# VIVA_PIC16_with_battery.net
KiCad netlist of a schematic drawn in EAGLE
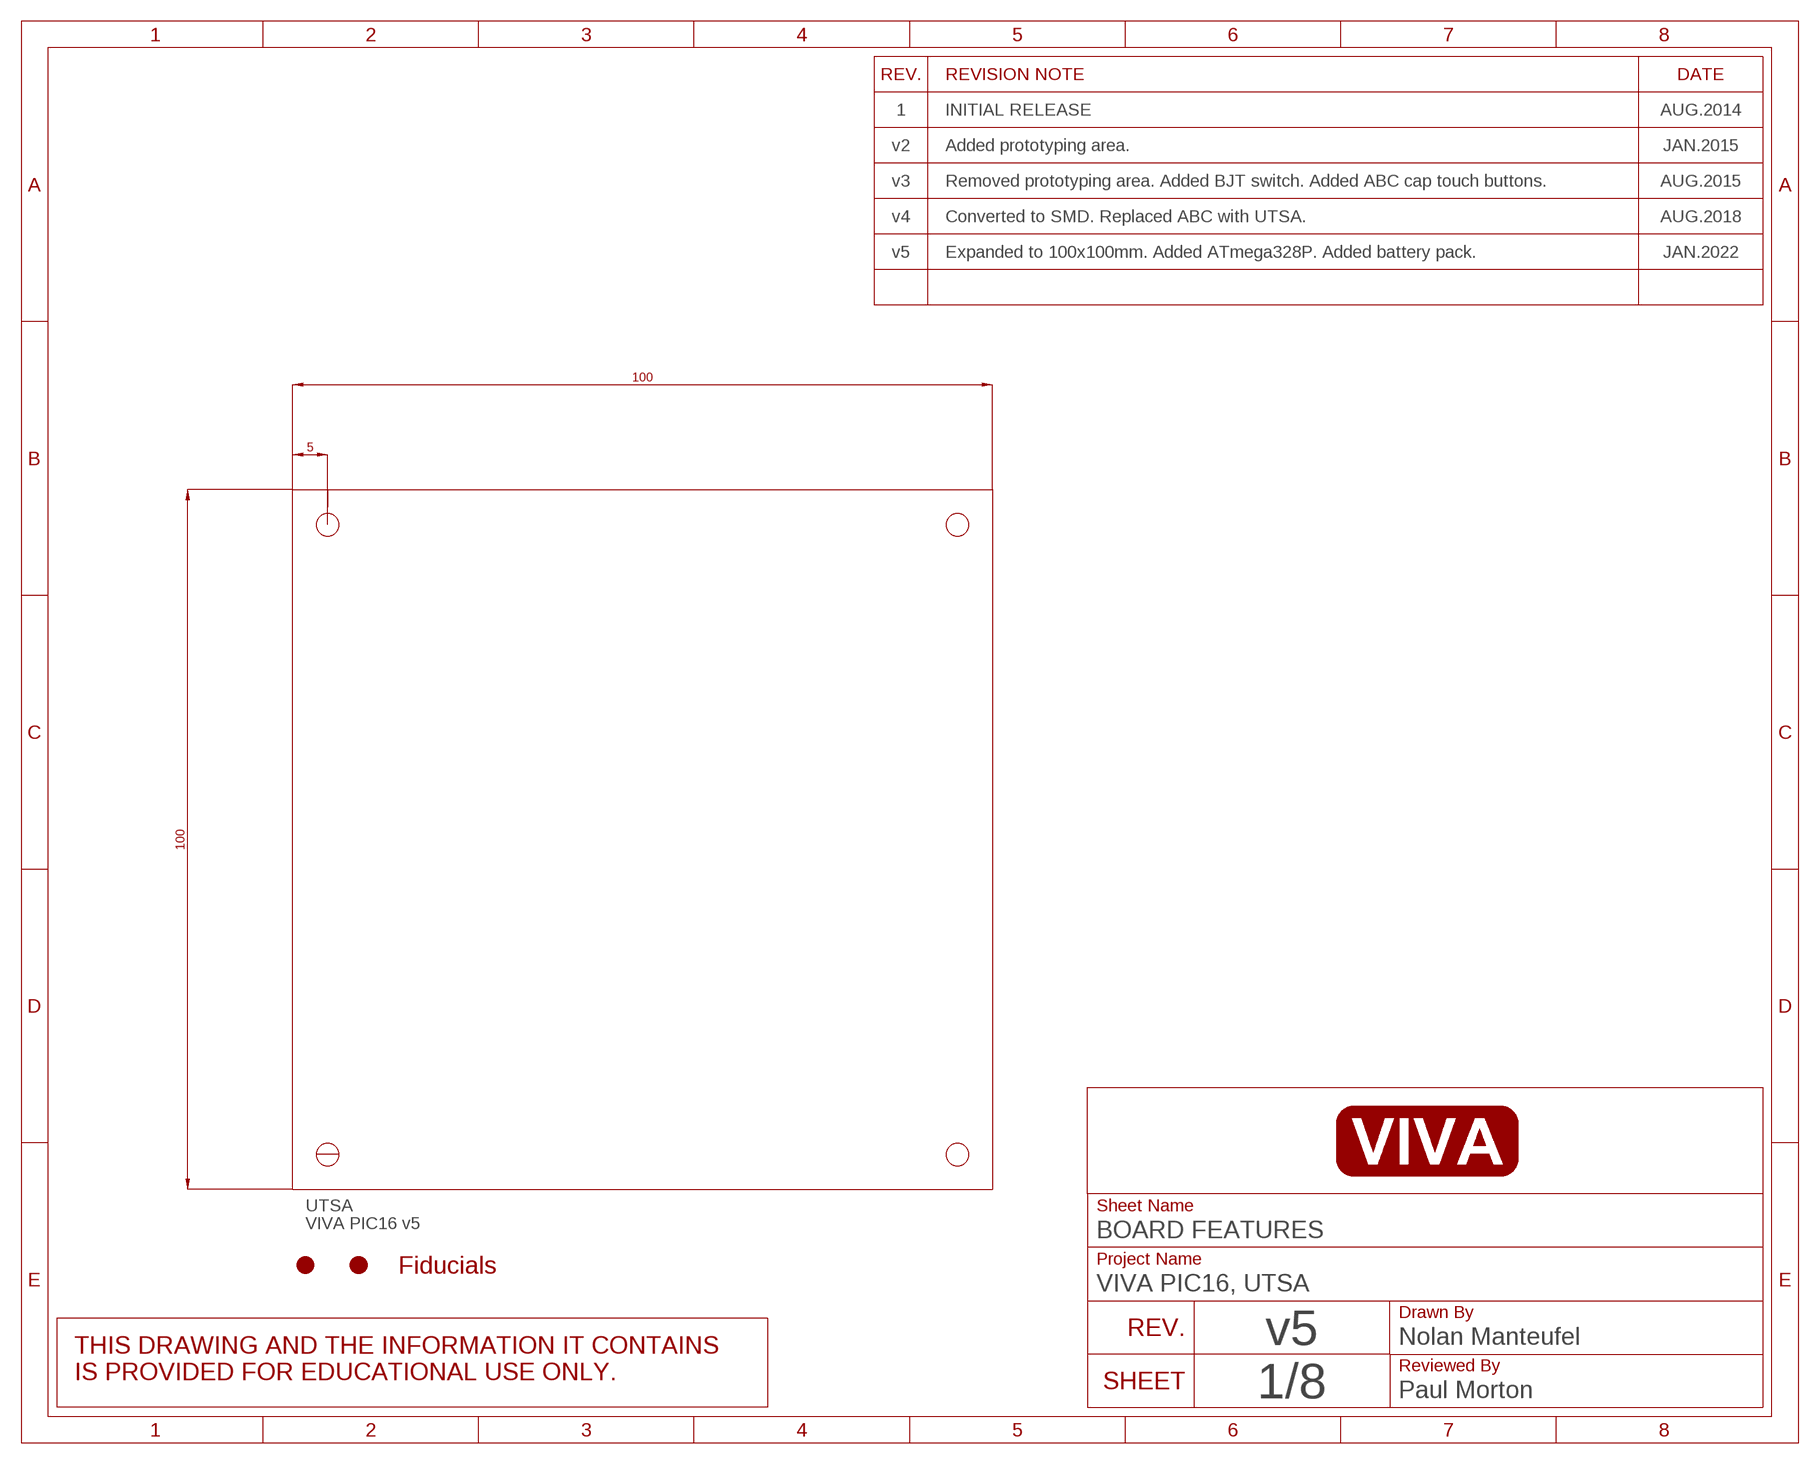
[diagram p0: schematic, sheet 1]
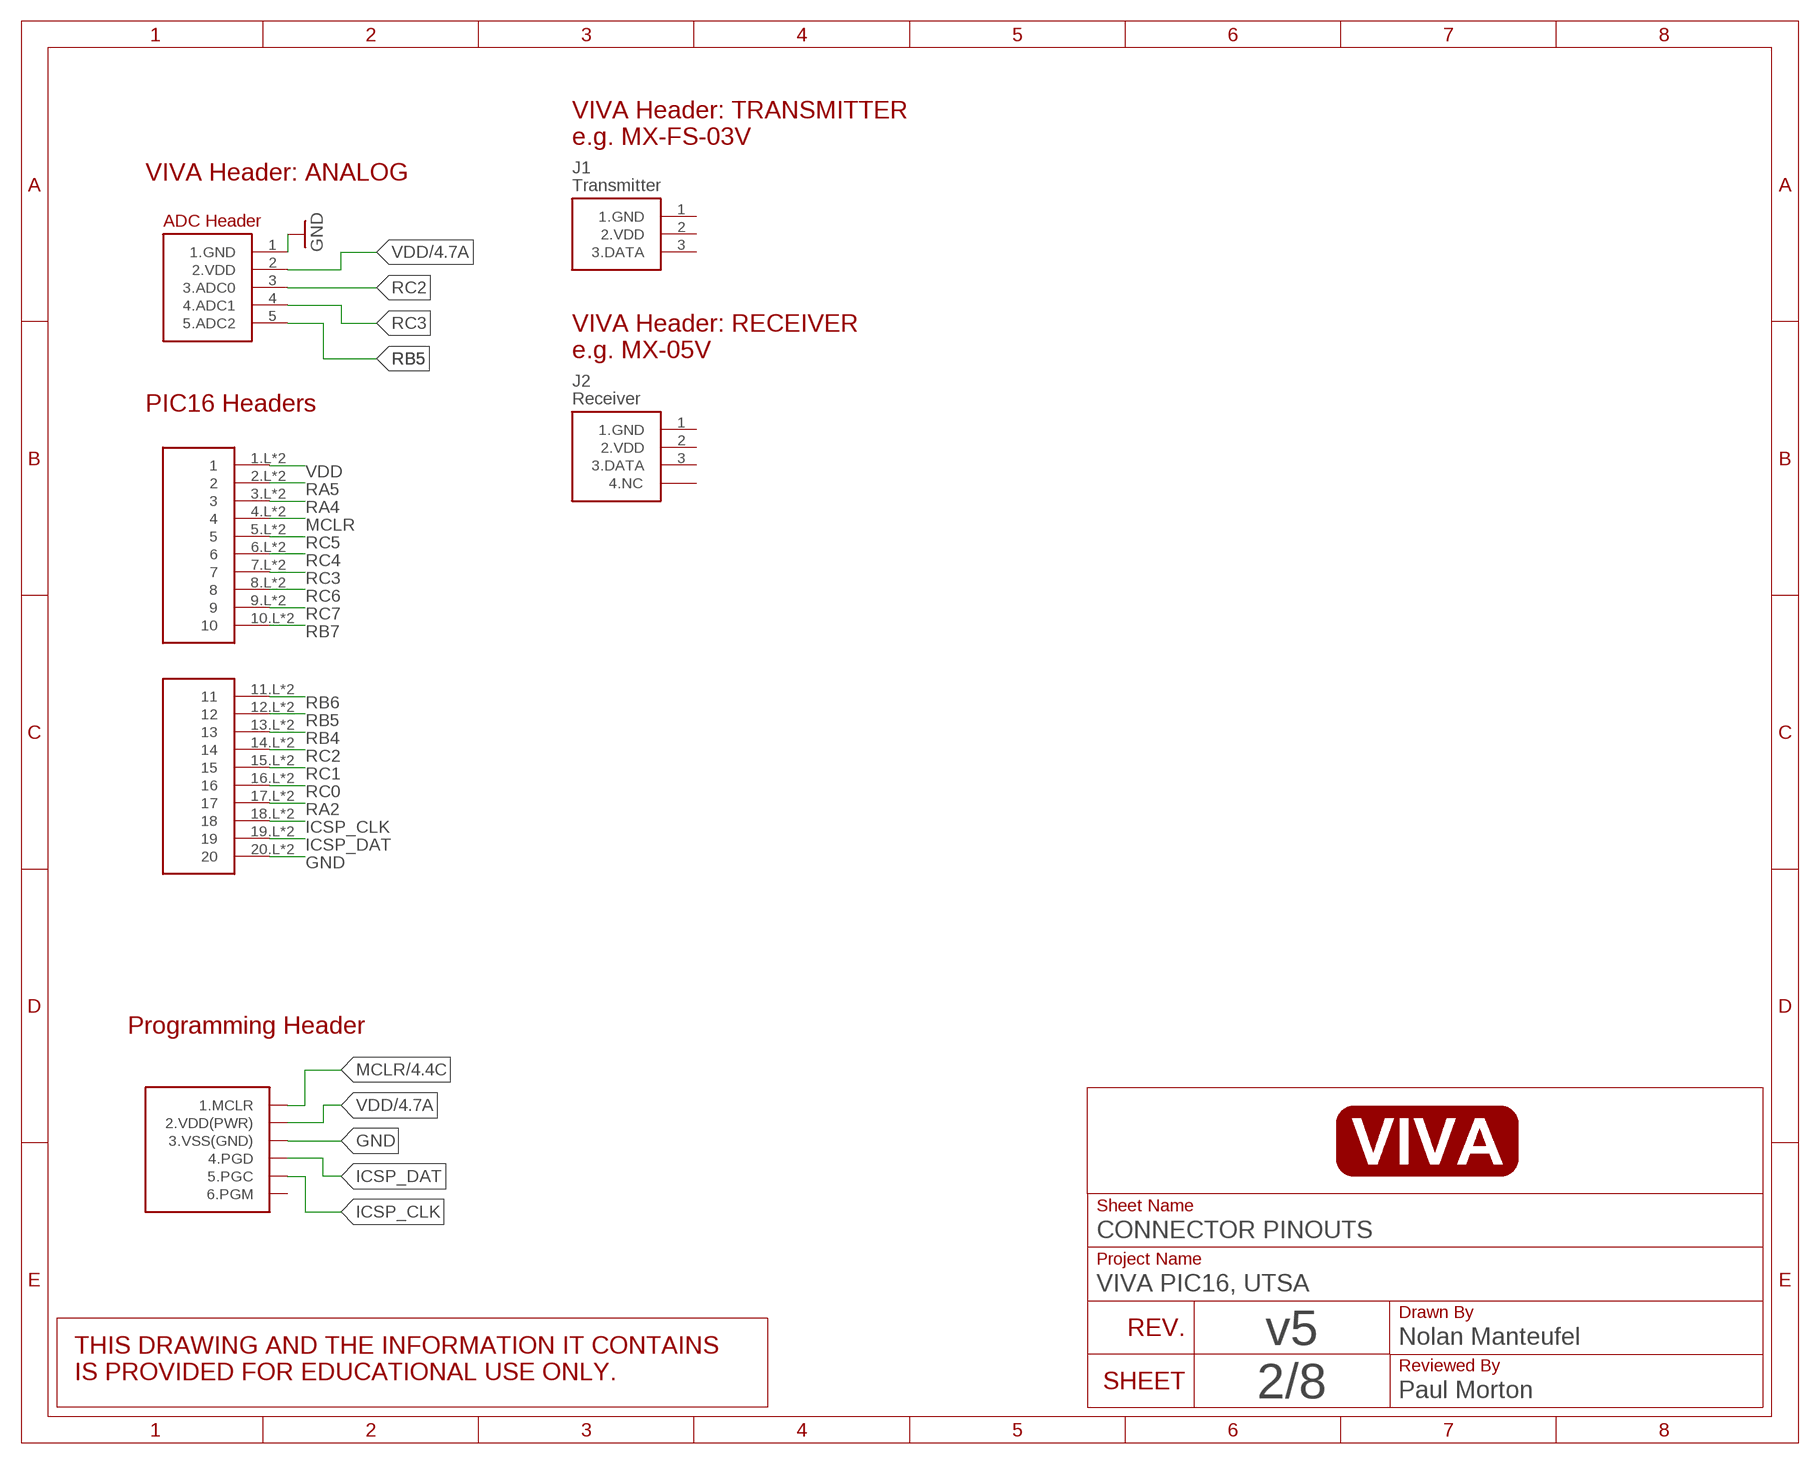
[diagram p1: schematic, sheet 2]
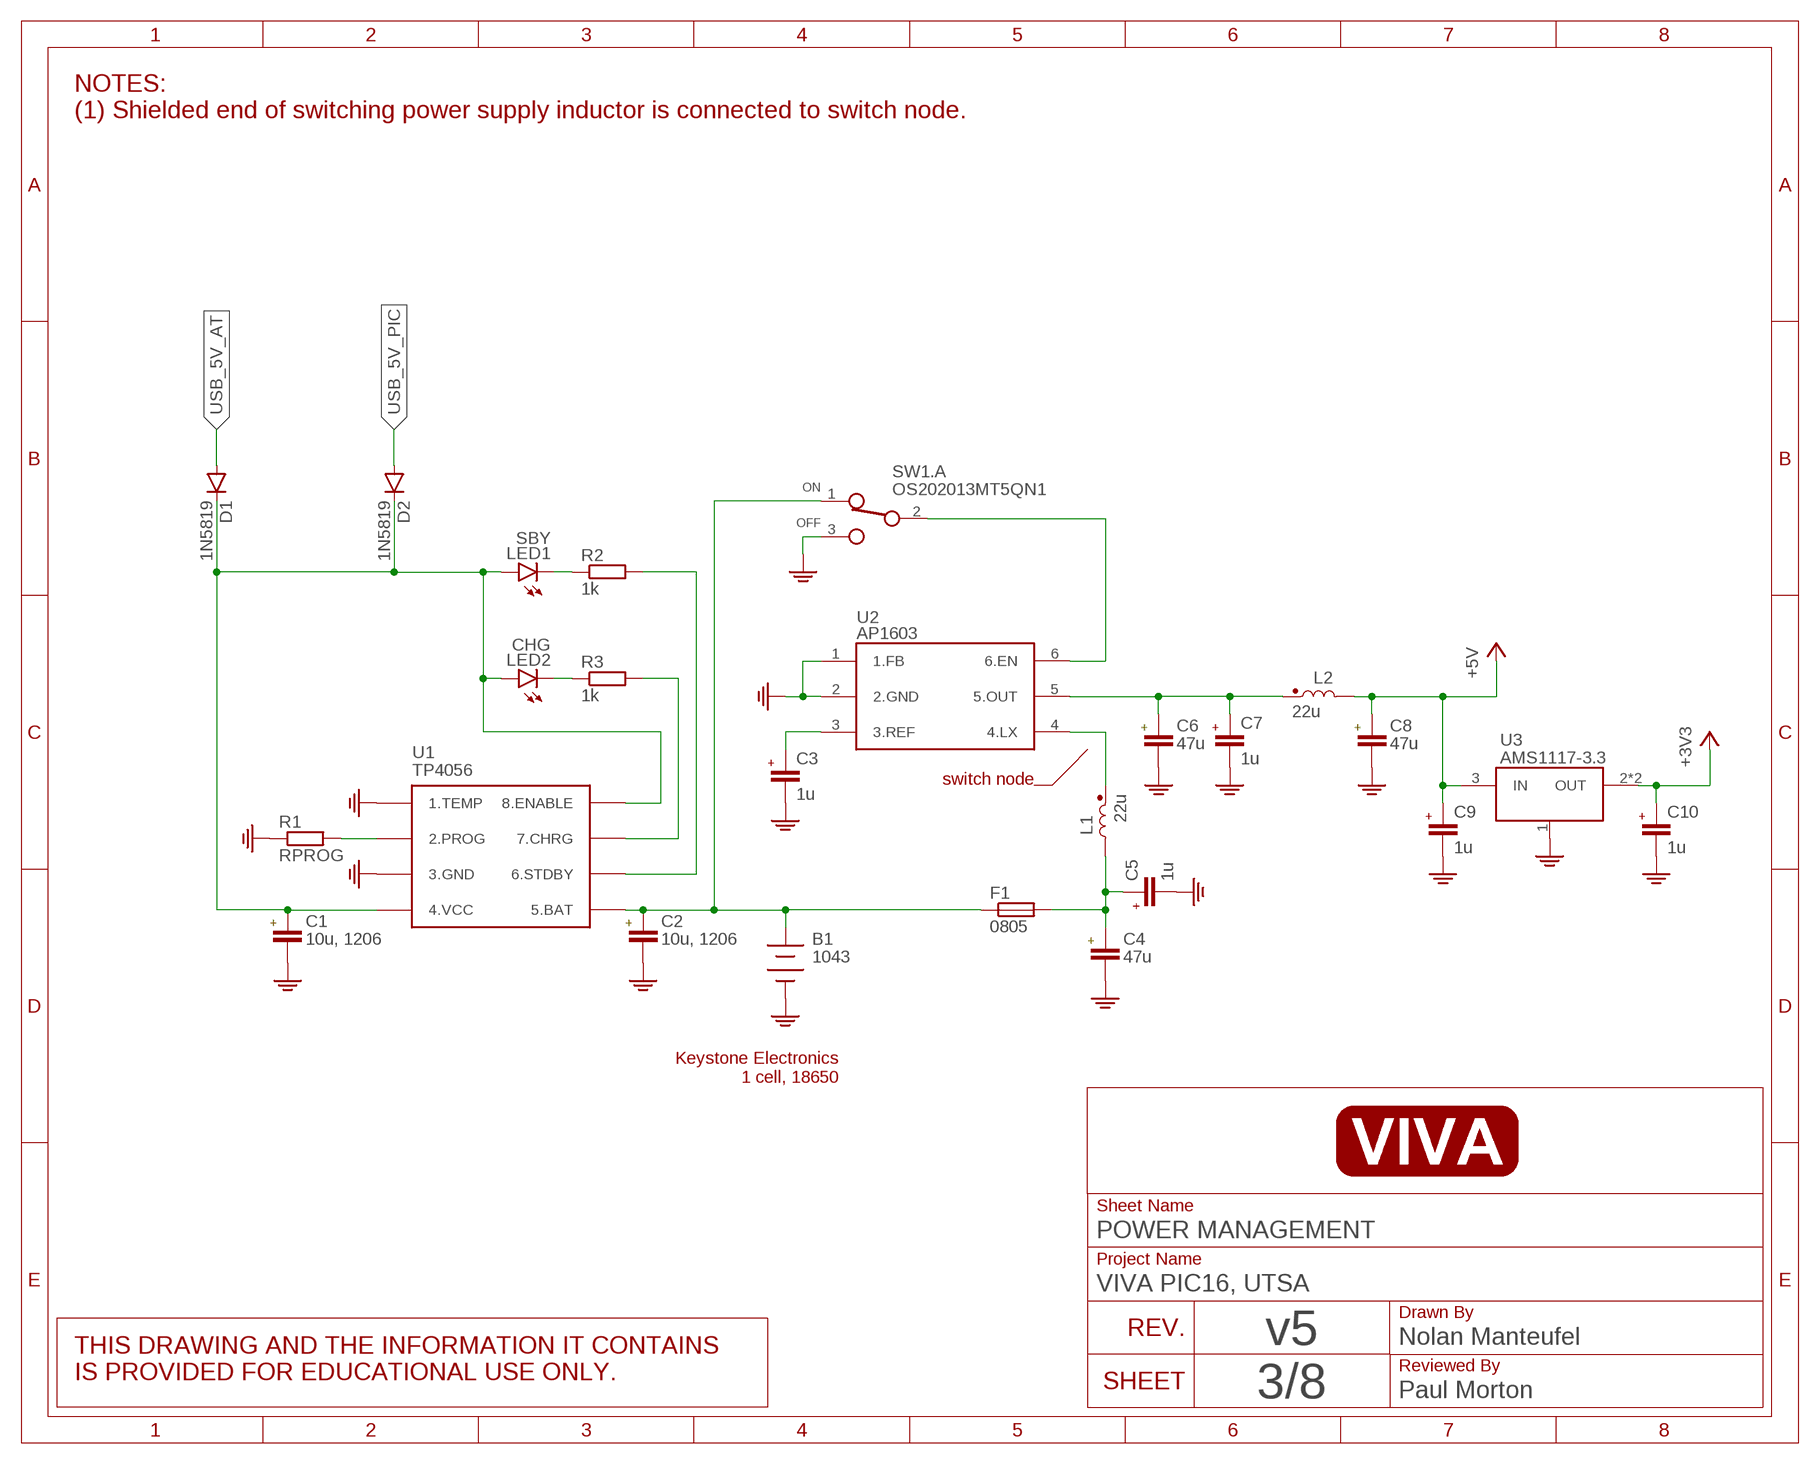
[diagram p2: schematic, sheet 3]
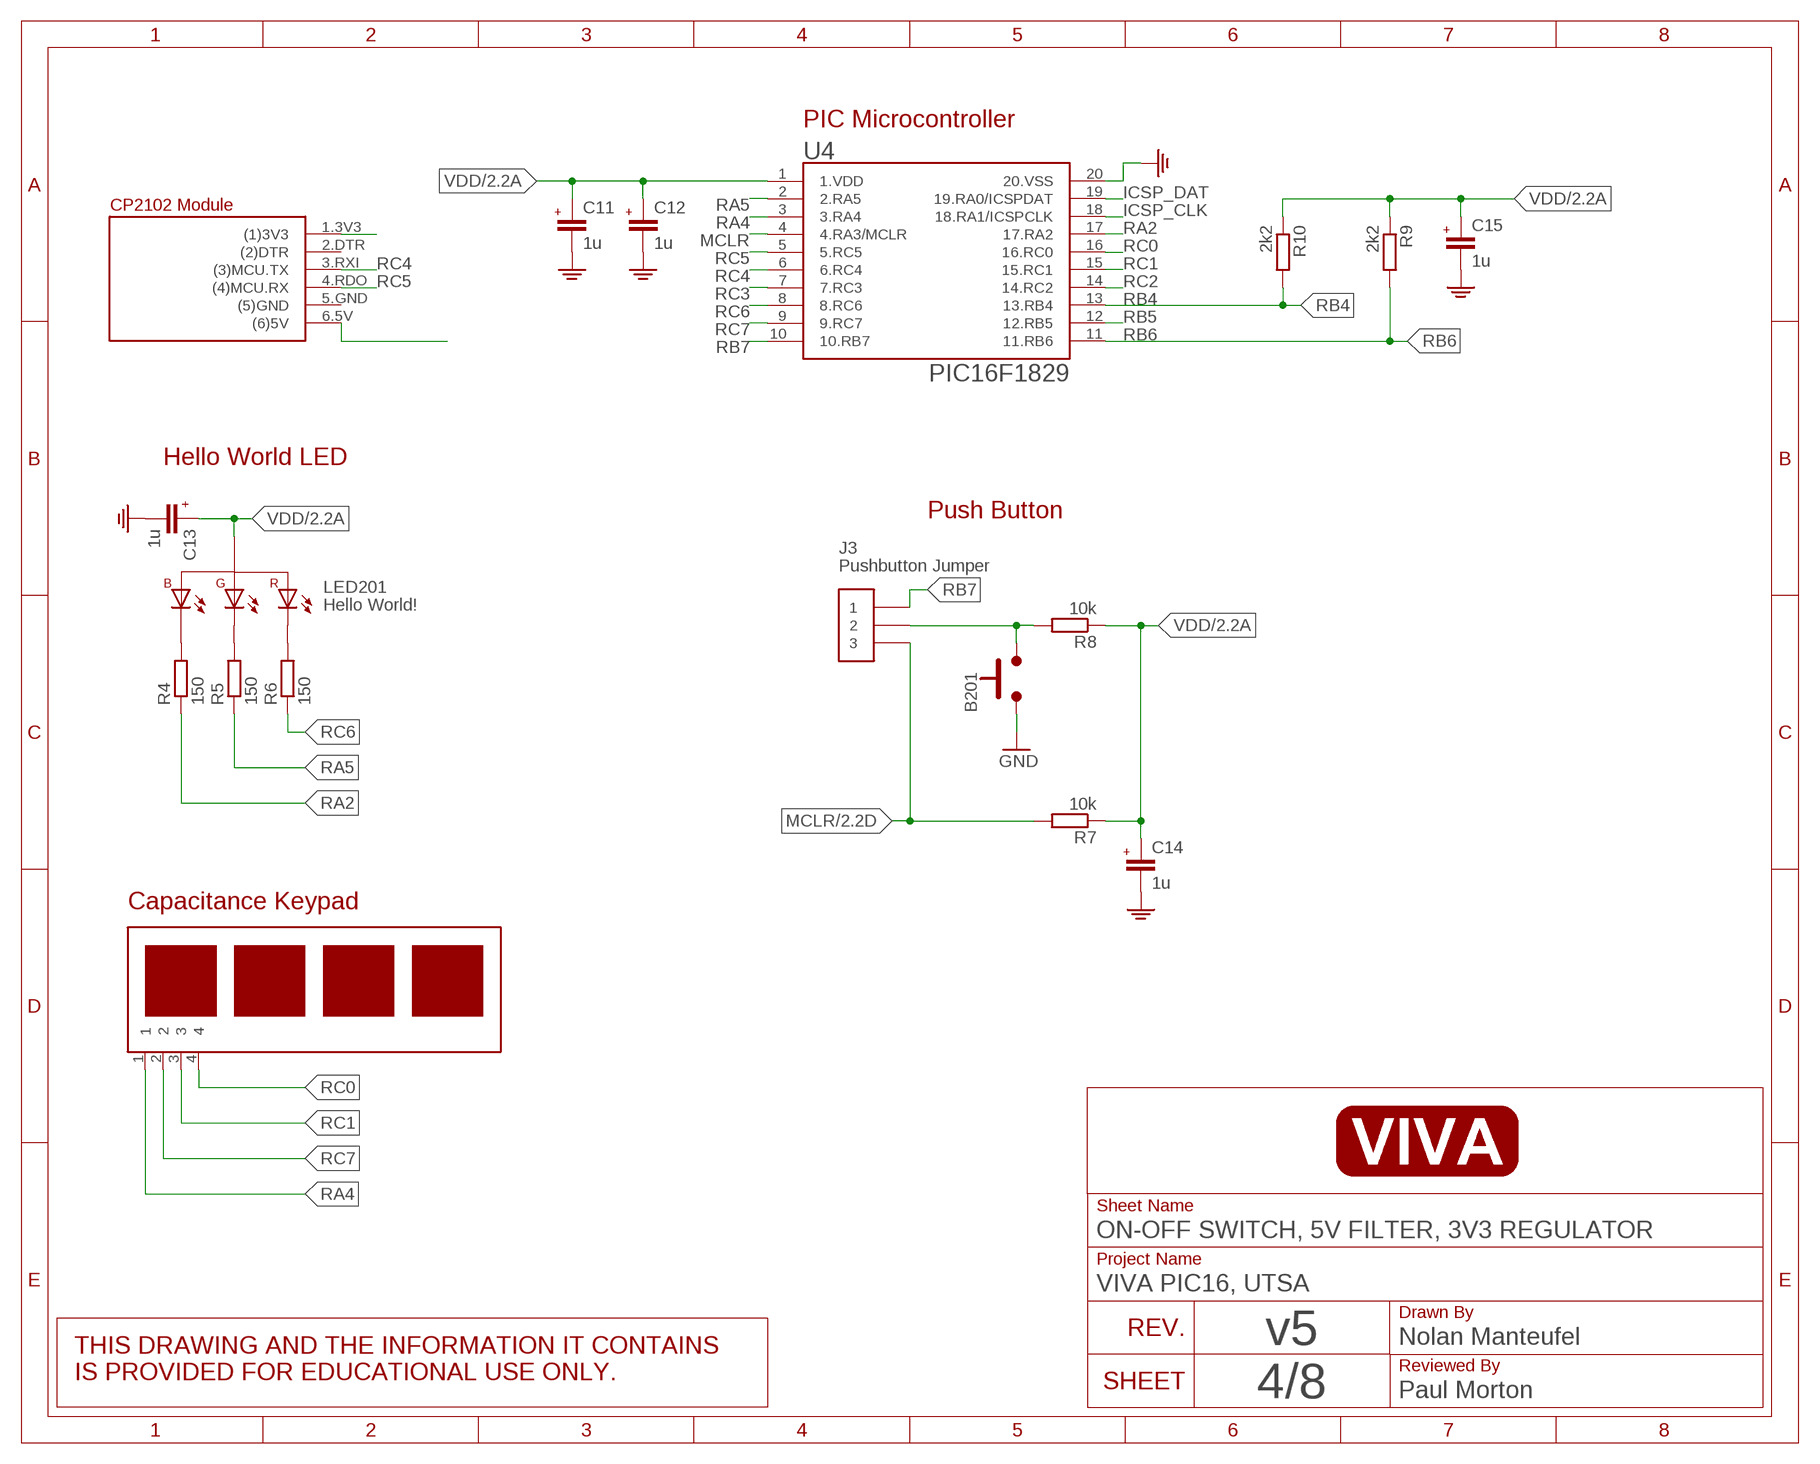
[diagram p3: schematic, sheet 4]
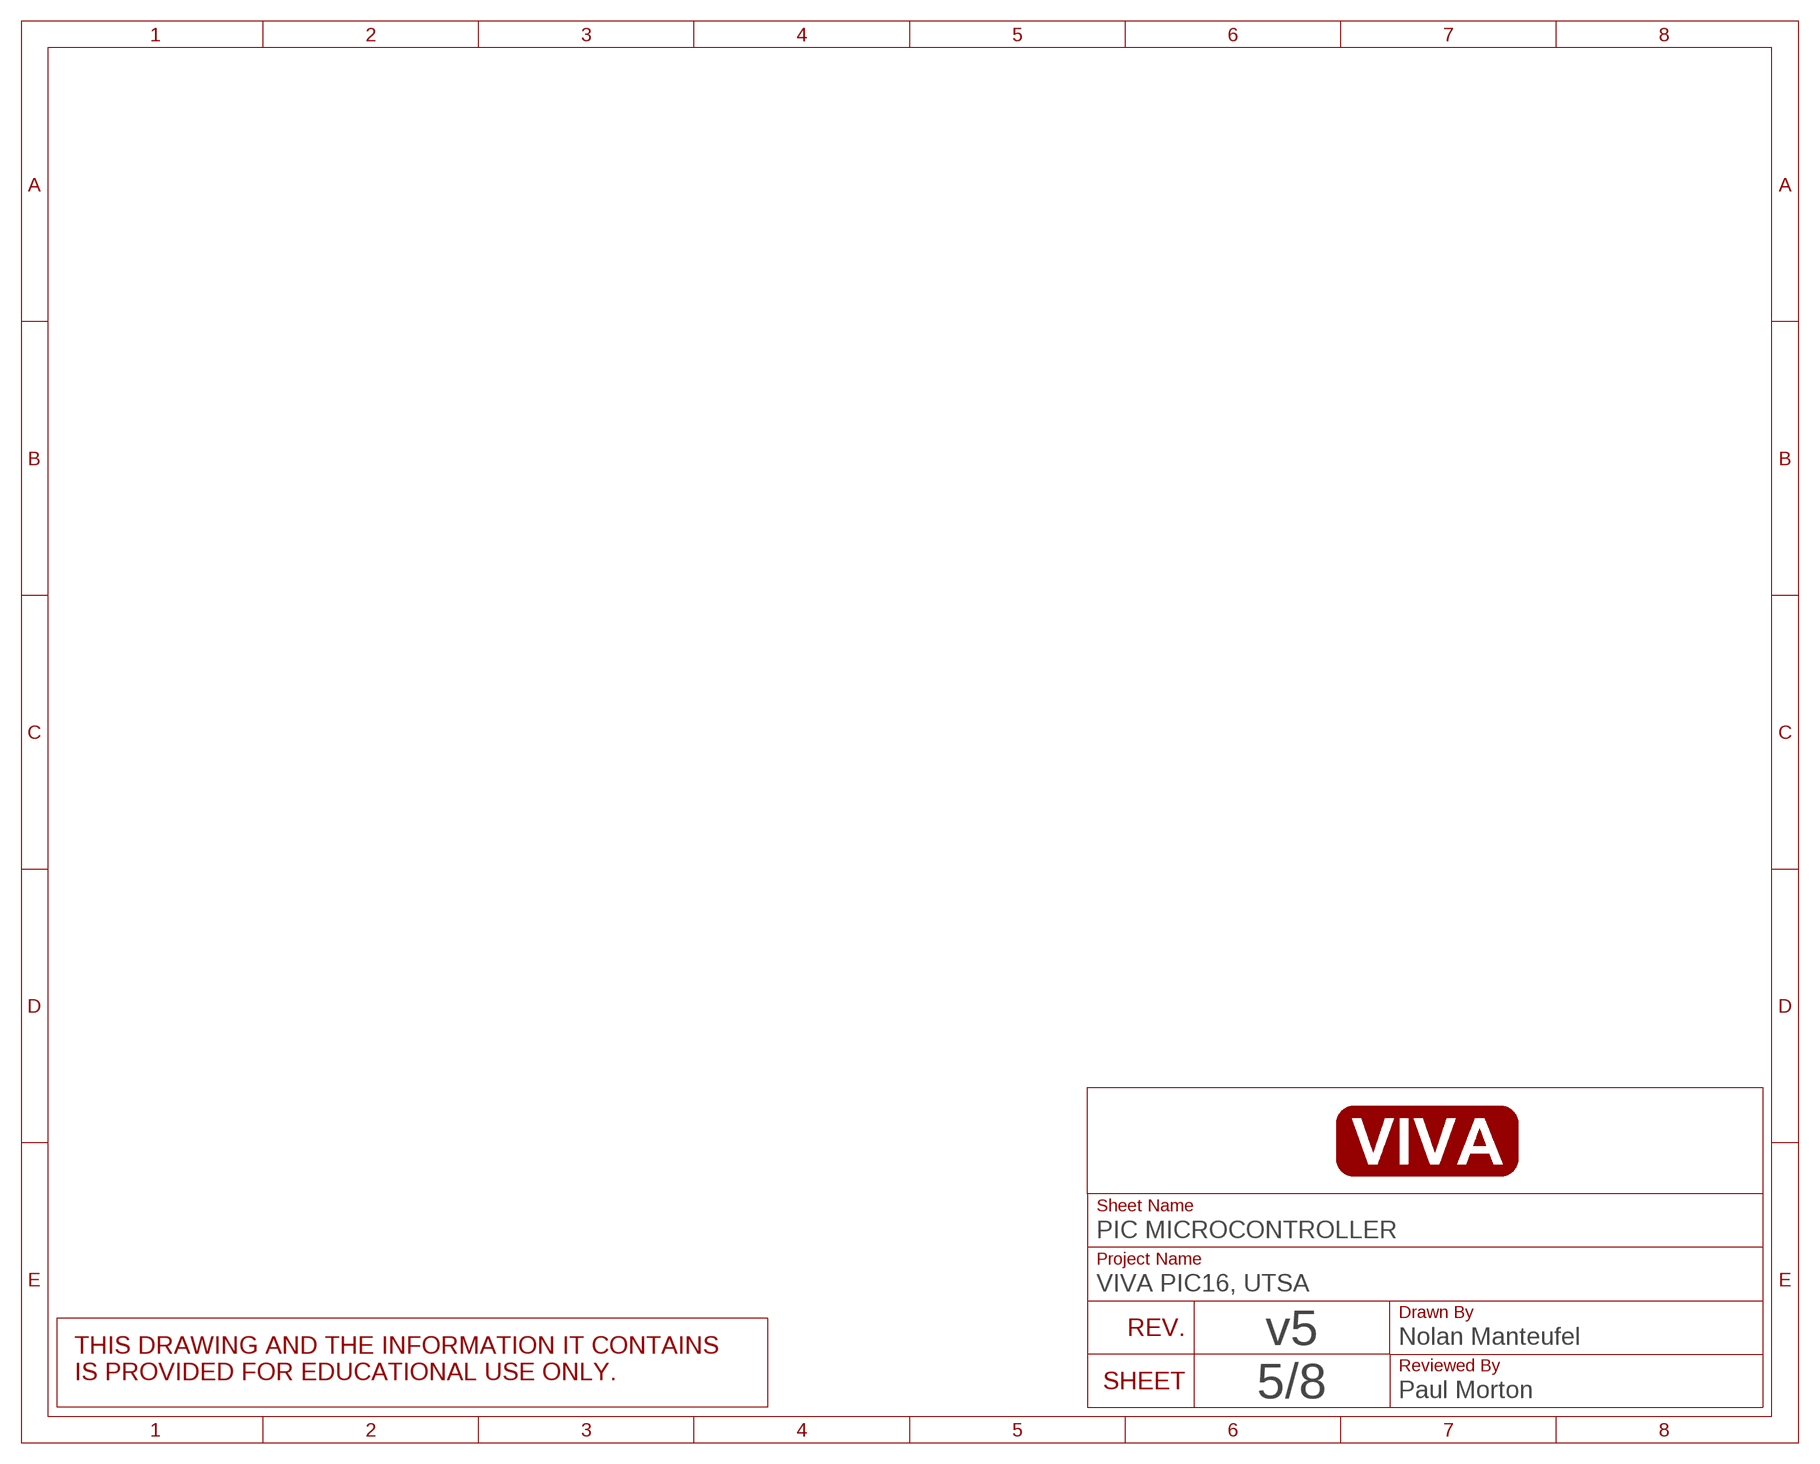
[diagram p4: schematic, sheet 5]
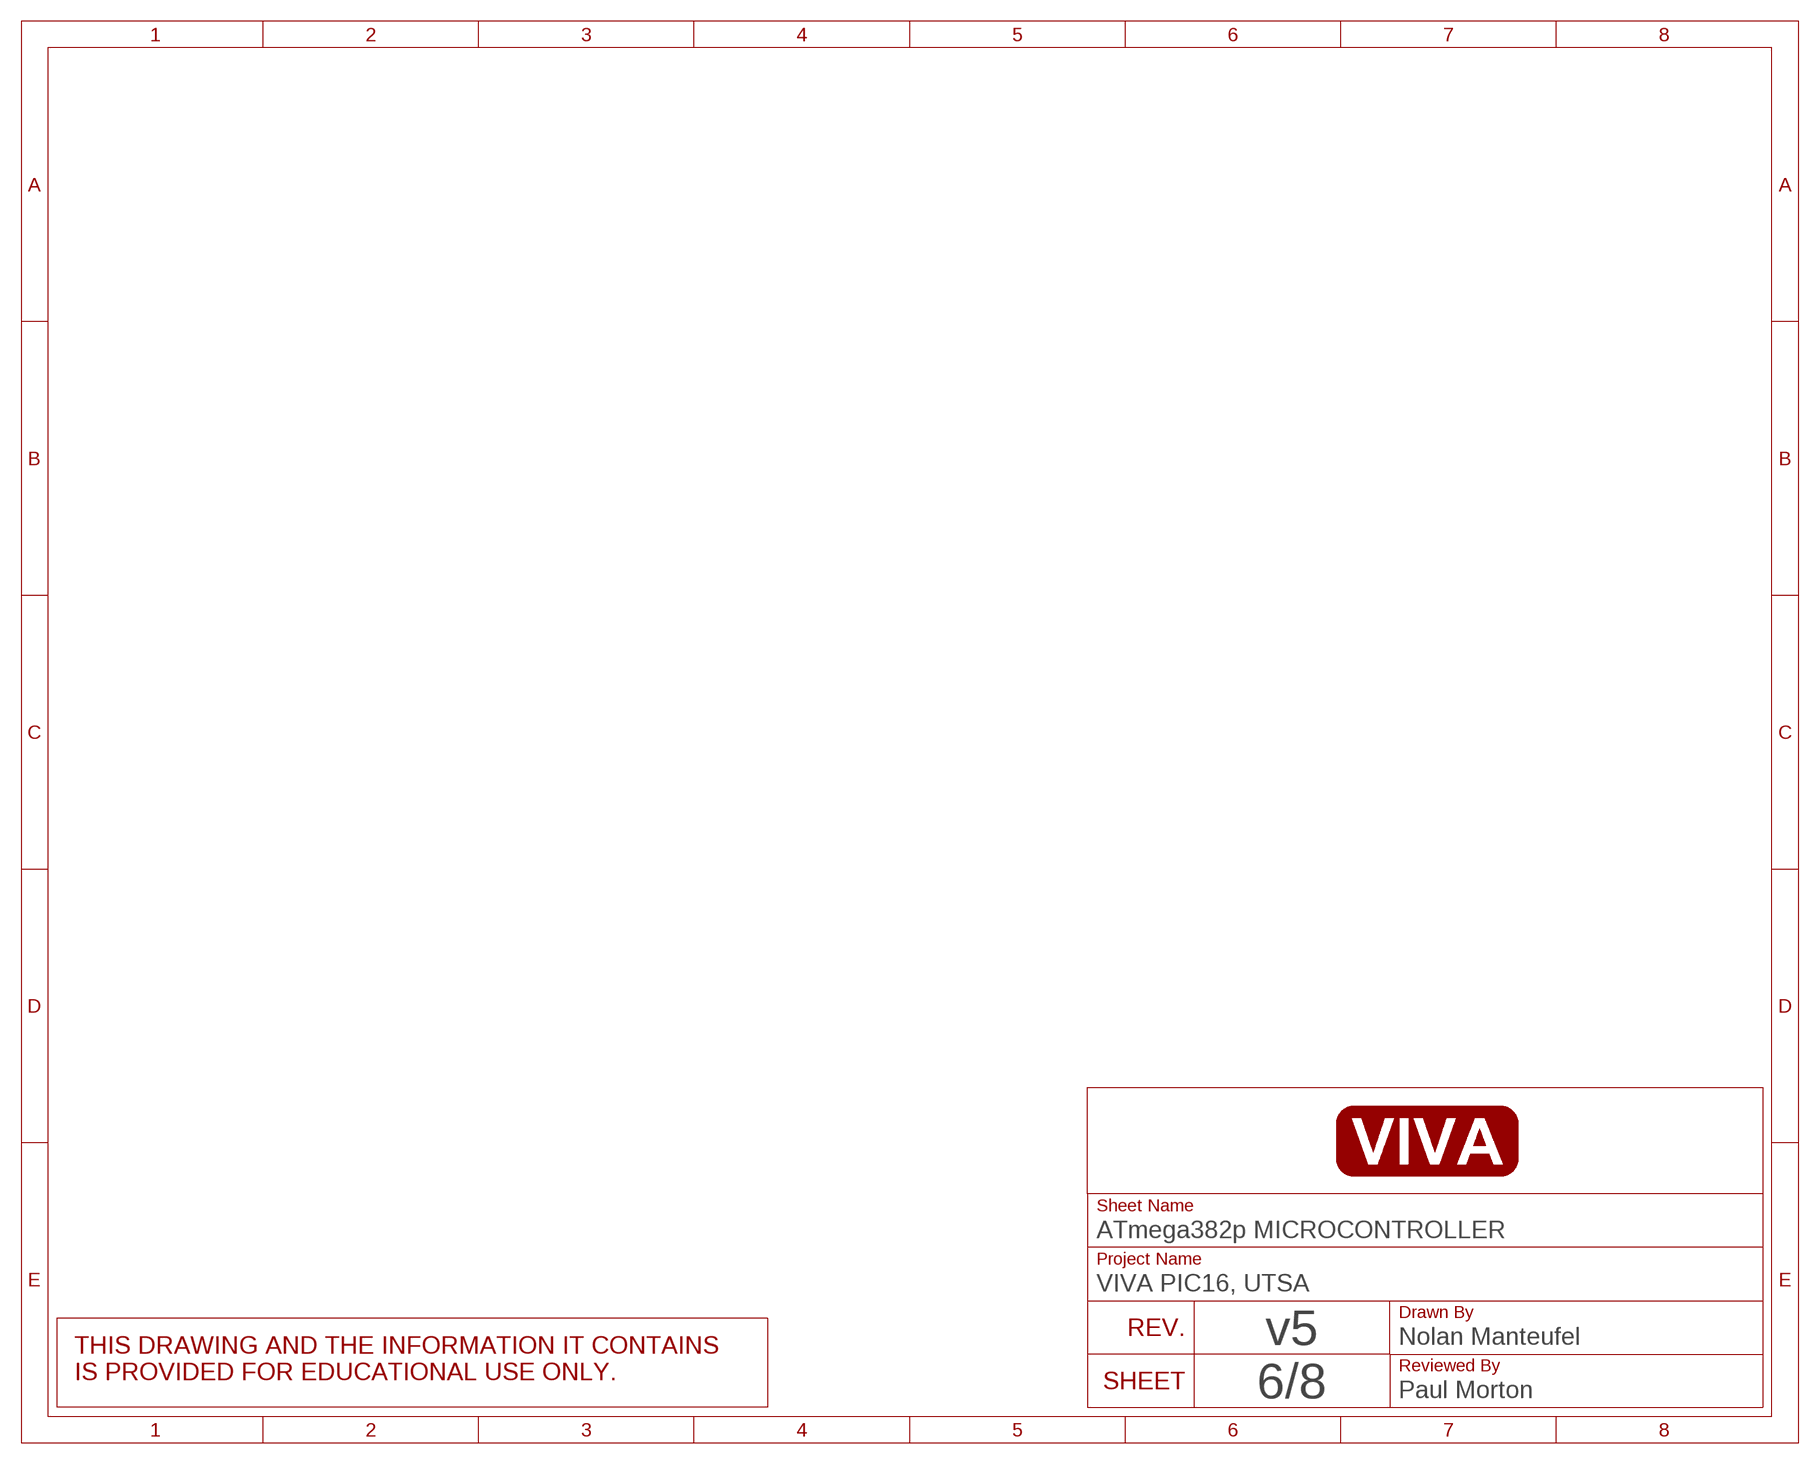
[diagram p5: schematic, sheet 6]
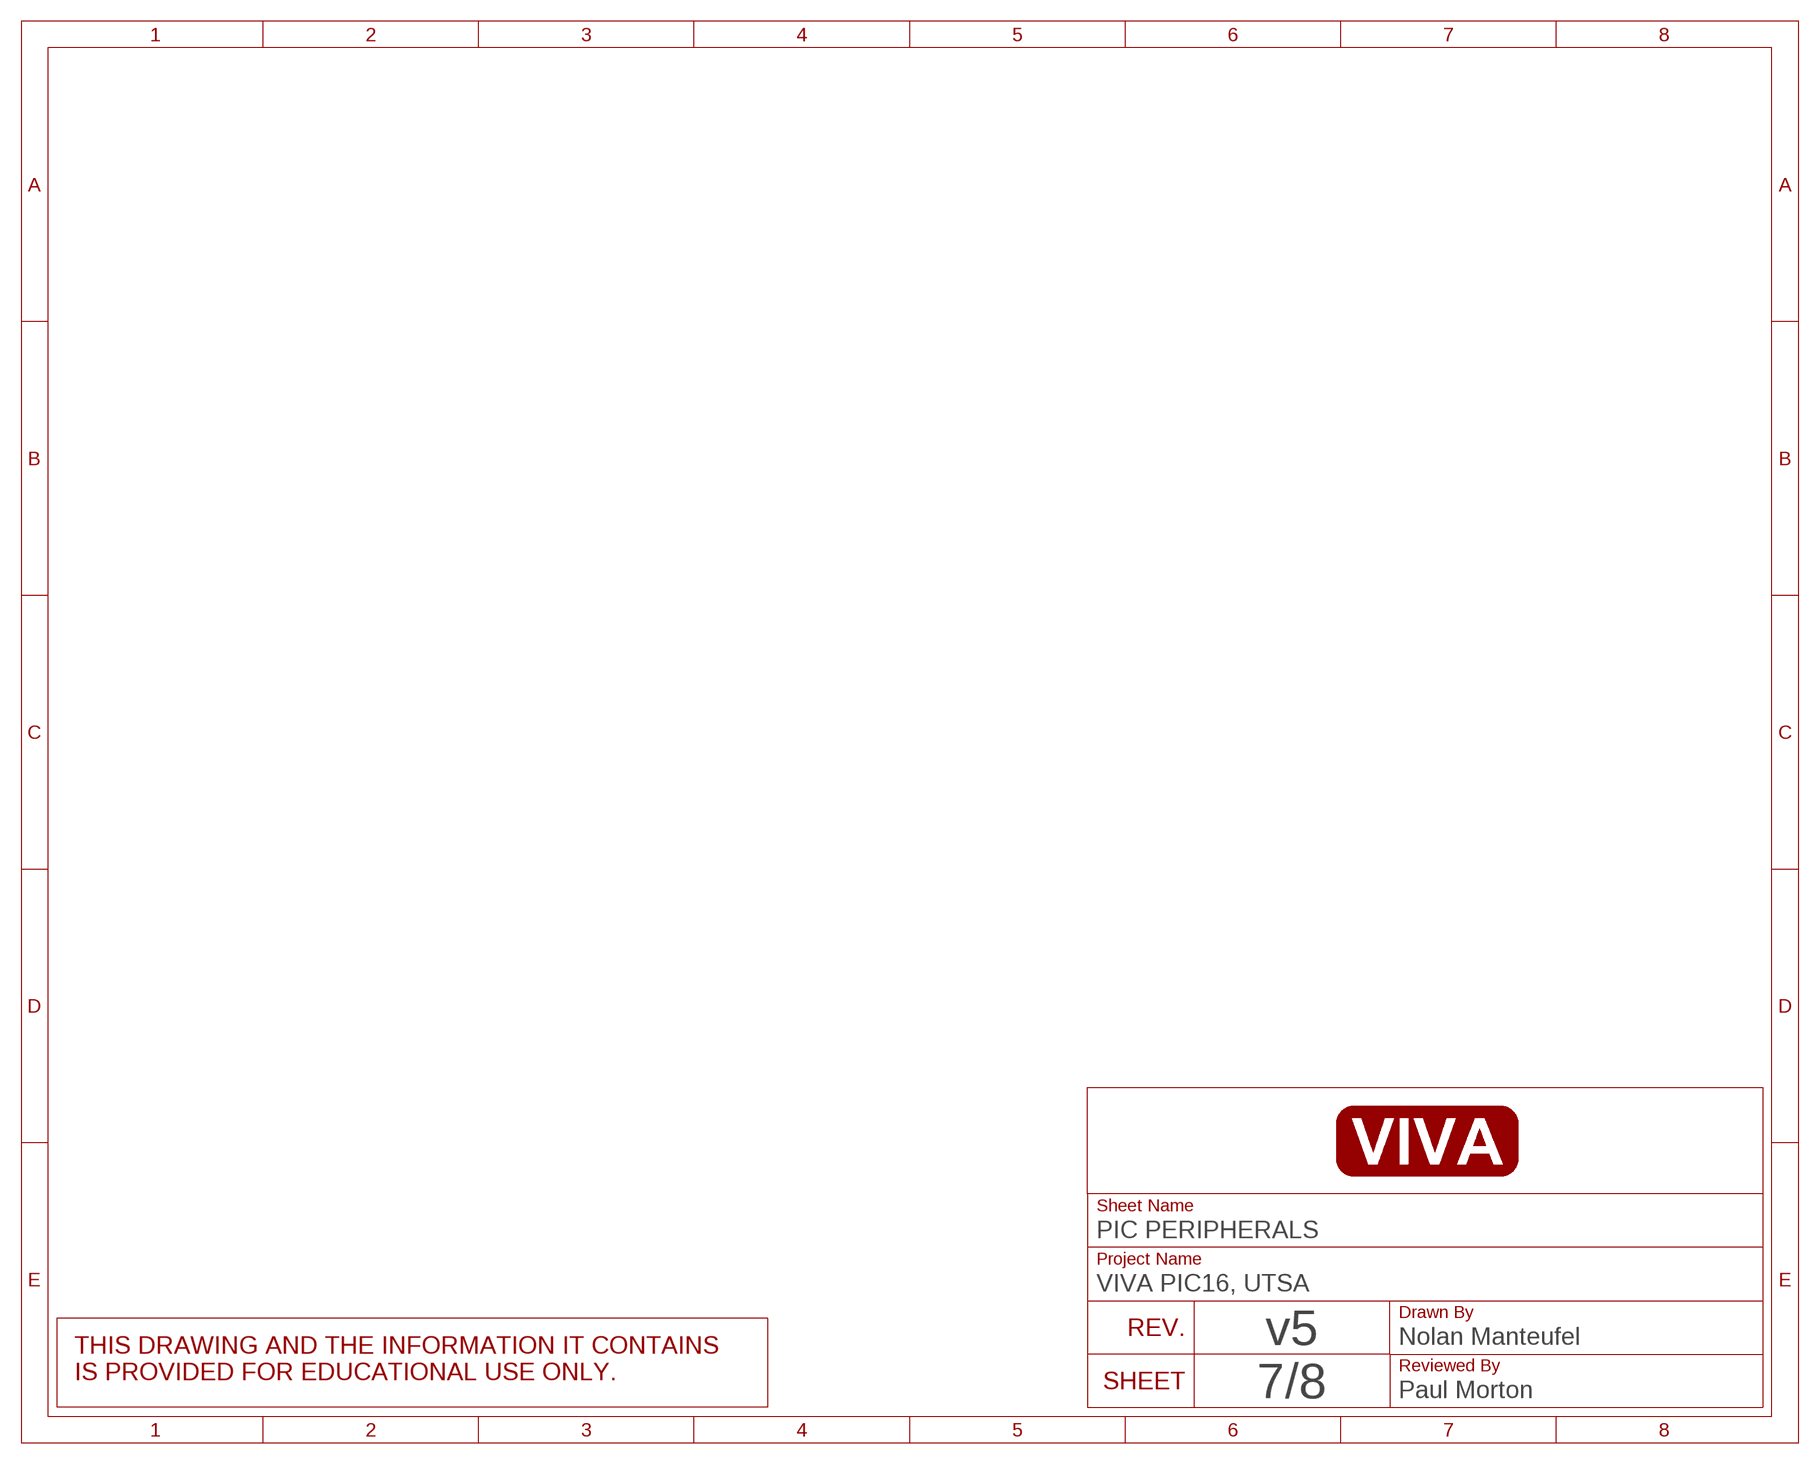
[diagram p6: schematic, sheet 7]
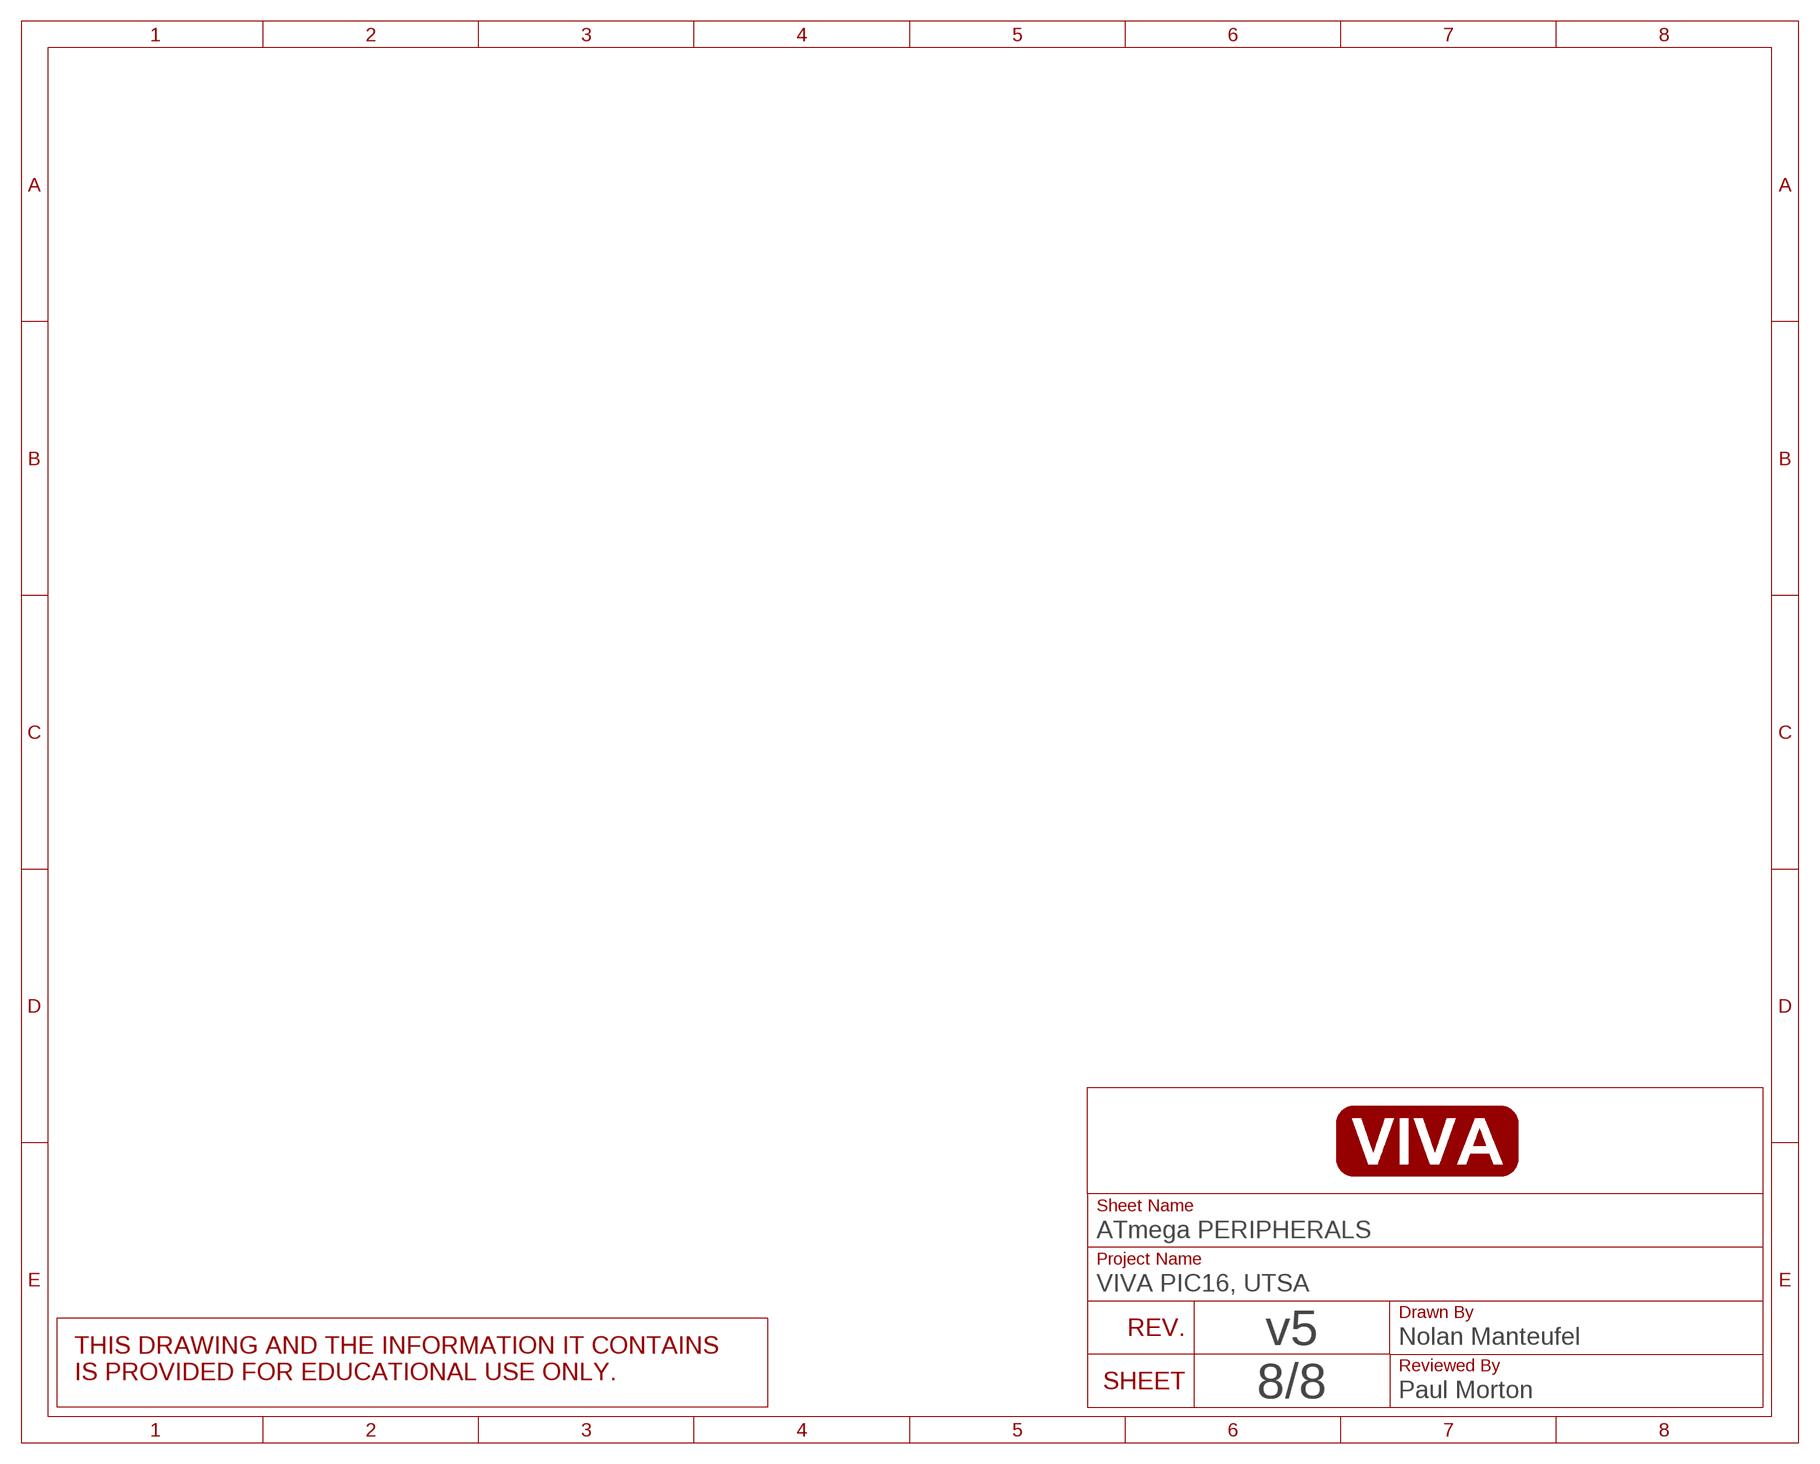
[diagram p7: schematic, sheet 8]

(export (version "E")
  (design (tool "Eeschema 10.0.6"))
  (components
    (comp (ref "J1")
      (value "Transmitter")
      (footprint "eagle-import:VIVA-HEADER-GPIO-RA-1")
      (libsource (lib "eagle-import") (part "VIVA-HEADER-GPIO-1"))
    )
    (comp (ref "J2")
      (value "Receiver")
      (footprint "eagle-import:VIVA-HEADER-RF-RX")
      (libsource (lib "eagle-import") (part "VIVA-HEADER-RF-RX"))
    )
    (comp (ref "J202")
      (value "VIVA-HEADER-ADCNONAME")
      (footprint "eagle-import:VIVA-HEADER-ADC-NONAME")
      (libsource (lib "eagle-import") (part "VIVA-HEADER-ADCNONAME"))
    )
    (comp (ref "J203")
      (value "PICKIT3")
      (footprint "eagle-import:PICKIT3")
      (libsource (lib "eagle-import") (part "PICKIT3"))
    )
    (comp (ref "U$6")
      (value "VIVA_PIC16BOARD")
      (footprint "eagle-import:VIVA_PIC16")
      (libsource (lib "eagle-import") (part "VIVA_PIC16BOARD"))
    )
    (comp (ref "B1")
      (value "1043")
      (footprint "eagle-import:BATTERY-18650-1")
      (libsource (lib "eagle-import") (part "BATTERY18650"))
    )
    (comp (ref "C1")
      (value "10u, 1206")
      (footprint "eagle-import:C1206")
      (libsource (lib "eagle-import") (part "C-EUC1206"))
    )
    (comp (ref "C2")
      (value "10u, 1206")
      (footprint "eagle-import:C1206")
      (libsource (lib "eagle-import") (part "C-EUC1206"))
    )
    (comp (ref "C3")
      (value "1u")
      (footprint "eagle-import:C0805")
      (libsource (lib "eagle-import") (part "C0805"))
    )
    (comp (ref "C4")
      (value "47u")
      (footprint "eagle-import:C-WE-5MM")
      (libsource (lib "eagle-import") (part "C-EU865080642006"))
    )
    (comp (ref "C5")
      (value "1u")
      (footprint "eagle-import:C0805")
      (libsource (lib "eagle-import") (part "C0805"))
    )
    (comp (ref "C6")
      (value "47u")
      (footprint "eagle-import:C-WE-5MM")
      (libsource (lib "eagle-import") (part "C-EU865080642006"))
    )
    (comp (ref "C7")
      (value "1u")
      (footprint "eagle-import:C0805")
      (libsource (lib "eagle-import") (part "C0805"))
    )
    (comp (ref "C8")
      (value "47u")
      (footprint "eagle-import:C-WE-5MM")
      (libsource (lib "eagle-import") (part "C-EU865080642006"))
    )
    (comp (ref "C9")
      (value "1u")
      (footprint "eagle-import:C0805")
      (libsource (lib "eagle-import") (part "C0805"))
    )
    (comp (ref "C10")
      (value "1u")
      (footprint "eagle-import:C0805")
      (libsource (lib "eagle-import") (part "C0805"))
    )
    (comp (ref "D1")
      (value "1N5819")
      (footprint "eagle-import:SOD80C")
      (libsource (lib "eagle-import") (part "DIODE-SOD80C"))
    )
    (comp (ref "D2")
      (value "1N5819")
      (footprint "eagle-import:SOD80C")
      (libsource (lib "eagle-import") (part "DIODE-SOD80C"))
    )
    (comp (ref "F1")
      (value "0805")
      (footprint "eagle-import:F0805")
      (libsource (lib "eagle-import") (part "FUSE0805"))
    )
    (comp (ref "L1")
      (value "22u")
      (footprint "eagle-import:SRN5040")
      (libsource (lib "eagle-import") (part "L5040"))
    )
    (comp (ref "L2")
      (value "22u")
      (footprint "eagle-import:SRN5040")
      (libsource (lib "eagle-import") (part "L5040"))
    )
    (comp (ref "LED1")
      (value "SBY")
      (footprint "eagle-import:CHIPLED_0603")
      (libsource (lib "eagle-import") (part "LEDCHIPLED_0603"))
    )
    (comp (ref "LED2")
      (value "CHG")
      (footprint "eagle-import:CHIPLED_0603")
      (libsource (lib "eagle-import") (part "LEDCHIPLED_0603"))
    )
    (comp (ref "R1")
      (value "RPROG")
      (footprint "eagle-import:R0805")
      (libsource (lib "eagle-import") (part "R-EU__R0805"))
    )
    (comp (ref "R2")
      (value "1k")
      (footprint "eagle-import:R0805")
      (libsource (lib "eagle-import") (part "R-EU__R0805"))
    )
    (comp (ref "R3")
      (value "1k")
      (footprint "eagle-import:R0805")
      (libsource (lib "eagle-import") (part "R-EU__R0805"))
    )
    (comp (ref "SW1.")
      (value "OS202013MT5QN1")
      (footprint "eagle-import:OS202013MT5QN1")
      (libsource (lib "eagle-import") (part "SWITCH_DPDT"))
    )
    (comp (ref "U1")
      (value "TP4056")
      (footprint "eagle-import:SO08-THERMAL")
      (libsource (lib "eagle-import") (part "TP4056"))
    )
    (comp (ref "U2")
      (value "AP1603")
      (footprint "eagle-import:SOT23-6")
      (libsource (lib "eagle-import") (part "AP1603"))
    )
    (comp (ref "U3")
      (value "AMS1117-3.3")
      (footprint "eagle-import:SOT223")
      (libsource (lib "eagle-import") (part "REGULATOR_SCHLM1117"))
    )
    (comp (ref "B201")
      (value "PUSHBUTTON6X6MM")
      (footprint "eagle-import:6X6MM")
      (libsource (lib "eagle-import") (part "PUSHBUTTON6X6MM"))
    )
    (comp (ref "C11")
      (value "1u")
      (footprint "eagle-import:C0805")
      (libsource (lib "eagle-import") (part "C0805"))
    )
    (comp (ref "C12")
      (value "1u")
      (footprint "eagle-import:C0805")
      (libsource (lib "eagle-import") (part "C0805"))
    )
    (comp (ref "C13")
      (value "1u")
      (footprint "eagle-import:C0805")
      (libsource (lib "eagle-import") (part "C0805"))
    )
    (comp (ref "C14")
      (value "1u")
      (footprint "eagle-import:C0805")
      (libsource (lib "eagle-import") (part "C0805"))
    )
    (comp (ref "C15")
      (value "1u")
      (footprint "eagle-import:C0805")
      (libsource (lib "eagle-import") (part "C0805"))
    )
    (comp (ref "J3")
      (value "Pushbutton Jumper")
      (footprint "eagle-import:PINS_3")
      (libsource (lib "eagle-import") (part "PINS_3_2.54"))
    )
    (comp (ref "LED201")
      (value "Hello World!")
      (footprint "eagle-import:LED_RGB-5050")
      (libsource (lib "eagle-import") (part "RGB_LED"))
    )
    (comp (ref "R4")
      (value "150")
      (footprint "eagle-import:R0805")
      (libsource (lib "eagle-import") (part "R-EU__R0805"))
    )
    (comp (ref "R5")
      (value "150")
      (footprint "eagle-import:R0805")
      (libsource (lib "eagle-import") (part "R-EU__R0805"))
    )
    (comp (ref "R6")
      (value "150")
      (footprint "eagle-import:R0805")
      (libsource (lib "eagle-import") (part "R-EU__R0805"))
    )
    (comp (ref "R7")
      (value "10k")
      (footprint "eagle-import:R0805")
      (libsource (lib "eagle-import") (part "R-EU__R0805"))
    )
    (comp (ref "R8")
      (value "10k")
      (footprint "eagle-import:R0805")
      (libsource (lib "eagle-import") (part "R-EU__R0805"))
    )
    (comp (ref "R9")
      (value "2k2")
      (footprint "eagle-import:R0805")
      (libsource (lib "eagle-import") (part "R-EU__R0805"))
    )
    (comp (ref "R10")
      (value "2k2")
      (footprint "eagle-import:R0805")
      (libsource (lib "eagle-import") (part "R-EU__R0805"))
    )
    (comp (ref "U$7")
      (value "VIVA_UTSA-KEYPADV5")
      (footprint "eagle-import:VIVA_UTSA-KEYPAD-V5")
      (libsource (lib "eagle-import") (part "VIVA_UTSA-KEYPADV5"))
    )
    (comp (ref "U$11")
      (value "VIVA_USB-TTL")
      (footprint "eagle-import:VIVA_USB_TTL_SUBTEXT")
      (libsource (lib "eagle-import") (part "VIVA_USB-TTL"))
    )
    (comp (ref "U4")
      (value "PIC16F1829")
      (footprint "eagle-import:SOP20-NEW")
      (libsource (lib "eagle-import") (part "PIC16F1829300"))
    )
    (comp (ref "FIDUCIAL1")
      (value "FIDUCIAL")
      (footprint "eagle-import:FIDUCIAL")
      (libsource (lib "eagle-import") (part "FIDUCIAL"))
    )
    (comp (ref "FIDUCIAL2")
      (value "FIDUCIAL")
      (footprint "eagle-import:FIDUCIAL")
      (libsource (lib "eagle-import") (part "FIDUCIAL"))
    )
    (comp (ref "UTSA")
      (value "VIVA PIC16 v5")
      (footprint "eagle-import:PCB_100X100")
      (libsource (lib "eagle-import") (part "PCB_100X100"))
    )
  )
  (nets
    (net (code "1") (name "+3V3") (class "Default")
      (node (ref "C10") (pin "2") (pinfunction "+_2") (pintype "passive"))
      (node (ref "U3") (pin "2") (pinfunction "OUT_2") (pintype "bidirectional"))
      (node (ref "U3") (pin "4.TAB") (pinfunction "OUT_4.TAB") (pintype "bidirectional"))
    )
    (net (code "2") (name "+5V") (class "Default")
      (node (ref "C8") (pin "1+") (pinfunction "1_1+") (pintype "passive"))
      (node (ref "C9") (pin "2") (pinfunction "+_2") (pintype "passive"))
      (node (ref "L2") (pin "1") (pinfunction "1_1") (pintype "passive"))
      (node (ref "U3") (pin "3") (pinfunction "IN_3") (pintype "bidirectional"))
    )
    (net (code "3") (name "GND") (class "Default")
      (node (ref "B1") (pin "1") (pinfunction "-_1") (pintype "bidirectional"))
      (node (ref "B201") (pin "1.A") (pinfunction "1_1.A") (pintype "bidirectional"))
      (node (ref "B201") (pin "2.A") (pinfunction "1_2.A") (pintype "bidirectional"))
      (node (ref "C1") (pin "-") (pinfunction "2_-") (pintype "passive"))
      (node (ref "C10") (pin "1") (pinfunction "-_1") (pintype "passive"))
      (node (ref "C11") (pin "1") (pinfunction "-_1") (pintype "passive"))
      (node (ref "C12") (pin "1") (pinfunction "-_1") (pintype "passive"))
      (node (ref "C13") (pin "1") (pinfunction "-_1") (pintype "passive"))
      (node (ref "C14") (pin "1") (pinfunction "-_1") (pintype "passive"))
      (node (ref "C15") (pin "1") (pinfunction "-_1") (pintype "passive"))
      (node (ref "C2") (pin "-") (pinfunction "2_-") (pintype "passive"))
      (node (ref "C3") (pin "1") (pinfunction "-_1") (pintype "passive"))
      (node (ref "C4") (pin "2-") (pinfunction "2_2-") (pintype "passive"))
      (node (ref "C5") (pin "1") (pinfunction "-_1") (pintype "passive"))
      (node (ref "C6") (pin "2-") (pinfunction "2_2-") (pintype "passive"))
      (node (ref "C7") (pin "1") (pinfunction "-_1") (pintype "passive"))
      (node (ref "C8") (pin "2-") (pinfunction "2_2-") (pintype "passive"))
      (node (ref "C9") (pin "1") (pinfunction "-_1") (pintype "passive"))
      (node (ref "J202") (pin "1") (pinfunction "1.GND_1") (pintype "bidirectional"))
      (node (ref "J203") (pin "3") (pinfunction "3.VSS(GND)_3") (pintype "bidirectional"))
      (node (ref "R1") (pin "1") (pinfunction "1_1") (pintype "passive"))
      (node (ref "SW1.") (pin "3") (pinfunction "OFF_3") (pintype "bidirectional"))
      (node (ref "U$6") (pin "20.L") (pinfunction "20_20.L") (pintype "bidirectional"))
      (node (ref "U$6") (pin "20.R") (pinfunction "20_20.R") (pintype "bidirectional"))
      (node (ref "U1") (pin "1") (pinfunction "1.TEMP_1") (pintype "bidirectional"))
      (node (ref "U1") (pin "3") (pinfunction "3.GND_3") (pintype "bidirectional"))
      (node (ref "U1") (pin "THERMAL") (pinfunction "3.GND_THERMAL") (pintype "bidirectional"))
      (node (ref "U2") (pin "1") (pinfunction "1.FB_1") (pintype "bidirectional"))
      (node (ref "U2") (pin "2") (pinfunction "2.GND_2") (pintype "bidirectional"))
      (node (ref "U3") (pin "1") (pinfunction "GND_1") (pintype "bidirectional"))
      (node (ref "U4") (pin "20") (pinfunction "20.VSS_20") (pintype "bidirectional"))
    )
    (net (code "4") (name "ICSP_CLK") (class "Default")
      (node (ref "J203") (pin "5") (pinfunction "5.PGC_5") (pintype "bidirectional"))
      (node (ref "U$6") (pin "18.L") (pinfunction "18_18.L") (pintype "bidirectional"))
      (node (ref "U$6") (pin "18.R") (pinfunction "18_18.R") (pintype "bidirectional"))
      (node (ref "U4") (pin "18") (pinfunction "18.RA1/ICSPCLK_18") (pintype "bidirectional"))
    )
    (net (code "5") (name "ICSP_DAT") (class "Default")
      (node (ref "J203") (pin "4") (pinfunction "4.PGD_4") (pintype "bidirectional"))
      (node (ref "U$6") (pin "19.L") (pinfunction "19_19.L") (pintype "bidirectional"))
      (node (ref "U$6") (pin "19.R") (pinfunction "19_19.R") (pintype "bidirectional"))
      (node (ref "U4") (pin "19") (pinfunction "19.RA0/ICSPDAT_19") (pintype "bidirectional"))
    )
    (net (code "6") (name "MCLR") (class "Default")
      (node (ref "J203") (pin "1") (pinfunction "1.MCLR_1") (pintype "bidirectional"))
      (node (ref "J3") (pin "3") (pinfunction "3_3") (pintype "bidirectional"))
      (node (ref "R7") (pin "2") (pinfunction "2_2") (pintype "passive"))
      (node (ref "U$6") (pin "4.L") (pinfunction "4_4.L") (pintype "bidirectional"))
      (node (ref "U$6") (pin "4.R") (pinfunction "4_4.R") (pintype "bidirectional"))
      (node (ref "U4") (pin "4") (pinfunction "4.RA3/MCLR_4") (pintype "bidirectional"))
    )
    (net (code "7") (name "Net-(B201-2-Pad3.B)") (class "Default")
      (node (ref "B201") (pin "3.B") (pinfunction "2_3.B") (pintype "bidirectional"))
      (node (ref "B201") (pin "4.B") (pinfunction "2_4.B") (pintype "bidirectional"))
      (node (ref "J3") (pin "2") (pinfunction "2_2") (pintype "bidirectional"))
      (node (ref "R8") (pin "2") (pinfunction "2_2") (pintype "passive"))
    )
    (net (code "8") (name "Net-(C1-1)") (class "Default")
      (node (ref "C1") (pin "+") (pinfunction "1_+") (pintype "passive"))
      (node (ref "D1") (pin "C") (pinfunction "C_C") (pintype "passive"))
      (node (ref "D2") (pin "C") (pinfunction "C_C") (pintype "passive"))
      (node (ref "LED1") (pin "A") (pinfunction "A_A") (pintype "passive"))
      (node (ref "LED2") (pin "A") (pinfunction "A_A") (pintype "passive"))
      (node (ref "U1") (pin "4") (pinfunction "4.VCC_4") (pintype "bidirectional"))
      (node (ref "U1") (pin "8") (pinfunction "8.ENABLE_8") (pintype "bidirectional"))
    )
    (net (code "9") (name "Net-(C2-1)") (class "Default")
      (node (ref "B1") (pin "+") (pinfunction "+_+") (pintype "bidirectional"))
      (node (ref "C2") (pin "+") (pinfunction "1_+") (pintype "passive"))
      (node (ref "F1") (pin "1") (pinfunction "1_1") (pintype "passive"))
      (node (ref "SW1.") (pin "1") (pinfunction "ON_1") (pintype "bidirectional"))
      (node (ref "U1") (pin "5") (pinfunction "5.BAT_5") (pintype "bidirectional"))
    )
    (net (code "10") (name "Net-(C3-+)") (class "Default")
      (node (ref "C3") (pin "2") (pinfunction "+_2") (pintype "passive"))
      (node (ref "U2") (pin "3") (pinfunction "3.REF_3") (pintype "bidirectional"))
    )
    (net (code "11") (name "Net-(C4-1)") (class "Default")
      (node (ref "C4") (pin "1+") (pinfunction "1_1+") (pintype "passive"))
      (node (ref "C5") (pin "2") (pinfunction "+_2") (pintype "passive"))
      (node (ref "F1") (pin "2") (pinfunction "2_2") (pintype "passive"))
      (node (ref "L1") (pin "1") (pinfunction "1_1") (pintype "passive"))
    )
    (net (code "12") (name "Net-(C6-1)") (class "Default")
      (node (ref "C6") (pin "1+") (pinfunction "1_1+") (pintype "passive"))
      (node (ref "C7") (pin "2") (pinfunction "+_2") (pintype "passive"))
      (node (ref "L2") (pin "2") (pinfunction "2_2") (pintype "passive"))
      (node (ref "U2") (pin "5") (pinfunction "5.OUT_5") (pintype "bidirectional"))
    )
    (net (code "13") (name "Net-(LED1-PadC)") (class "Default")
      (node (ref "LED1") (pin "C") (pinfunction "C_C") (pintype "passive"))
      (node (ref "R2") (pin "1") (pinfunction "1_1") (pintype "passive"))
    )
    (net (code "14") (name "Net-(LED2-PadC)") (class "Default")
      (node (ref "LED2") (pin "C") (pinfunction "C_C") (pintype "passive"))
      (node (ref "R3") (pin "1") (pinfunction "1_1") (pintype "passive"))
    )
    (net (code "15") (name "Net-(LED201-Pad1.R-)") (class "Default")
      (node (ref "LED201") (pin "1.R-") (pinfunction "1.R-_1.R-") (pintype "passive"))
      (node (ref "R6") (pin "2") (pinfunction "2_2") (pintype "passive"))
    )
    (net (code "16") (name "Net-(LED201-Pad2.G-)") (class "Default")
      (node (ref "LED201") (pin "2.G-") (pinfunction "2.G-_2.G-") (pintype "passive"))
      (node (ref "R5") (pin "2") (pinfunction "2_2") (pintype "passive"))
    )
    (net (code "17") (name "Net-(LED201-Pad4.B-)") (class "Default")
      (node (ref "LED201") (pin "4.B-") (pinfunction "4.B-_4.B-") (pintype "passive"))
      (node (ref "R4") (pin "2") (pinfunction "2_2") (pintype "passive"))
    )
    (net (code "18") (name "Net-(SW1.A-IN)") (class "Default")
      (node (ref "SW1.") (pin "2") (pinfunction "IN_2") (pintype "bidirectional"))
      (node (ref "U2") (pin "6") (pinfunction "6.EN_6") (pintype "bidirectional"))
    )
    (net (code "19") (name "Net-(U1-2.PROG)") (class "Default")
      (node (ref "R1") (pin "2") (pinfunction "2_2") (pintype "passive"))
      (node (ref "U1") (pin "2") (pinfunction "2.PROG_2") (pintype "bidirectional"))
    )
    (net (code "20") (name "Net-(U1-6.STDBY)") (class "Default")
      (node (ref "R2") (pin "2") (pinfunction "2_2") (pintype "passive"))
      (node (ref "U1") (pin "6") (pinfunction "6.STDBY_6") (pintype "bidirectional"))
    )
    (net (code "21") (name "Net-(U1-7.CHRG)") (class "Default")
      (node (ref "R3") (pin "2") (pinfunction "2_2") (pintype "passive"))
      (node (ref "U1") (pin "7") (pinfunction "7.CHRG_7") (pintype "bidirectional"))
    )
    (net (code "22") (name "Net-(U2-4.LX)") (class "Default")
      (node (ref "L1") (pin "2") (pinfunction "2_2") (pintype "passive"))
      (node (ref "U2") (pin "4") (pinfunction "4.LX_4") (pintype "bidirectional"))
    )
    (net (code "23") (name "RA2") (class "Default")
      (node (ref "R4") (pin "1") (pinfunction "1_1") (pintype "passive"))
      (node (ref "U$6") (pin "17.L") (pinfunction "17_17.L") (pintype "bidirectional"))
      (node (ref "U$6") (pin "17.R") (pinfunction "17_17.R") (pintype "bidirectional"))
      (node (ref "U4") (pin "17") (pinfunction "17.RA2_17") (pintype "bidirectional"))
    )
    (net (code "24") (name "RA4") (class "Default")
      (node (ref "U$6") (pin "3.L") (pinfunction "3_3.L") (pintype "bidirectional"))
      (node (ref "U$6") (pin "3.R") (pinfunction "3_3.R") (pintype "bidirectional"))
      (node (ref "U$7") (pin "1") (pinfunction "1_1") (pintype "bidirectional"))
      (node (ref "U4") (pin "3") (pinfunction "3.RA4_3") (pintype "bidirectional"))
    )
    (net (code "25") (name "RA5") (class "Default")
      (node (ref "R5") (pin "1") (pinfunction "1_1") (pintype "passive"))
      (node (ref "U$6") (pin "2.L") (pinfunction "2_2.L") (pintype "bidirectional"))
      (node (ref "U$6") (pin "2.R") (pinfunction "2_2.R") (pintype "bidirectional"))
      (node (ref "U4") (pin "2") (pinfunction "2.RA5_2") (pintype "bidirectional"))
    )
    (net (code "26") (name "RB4") (class "Default")
      (node (ref "R10") (pin "2") (pinfunction "2_2") (pintype "passive"))
      (node (ref "U$6") (pin "13.L") (pinfunction "13_13.L") (pintype "bidirectional"))
      (node (ref "U$6") (pin "13.R") (pinfunction "13_13.R") (pintype "bidirectional"))
      (node (ref "U4") (pin "13") (pinfunction "13.RB4_13") (pintype "bidirectional"))
    )
    (net (code "27") (name "RB5") (class "Default")
      (node (ref "J202") (pin "5") (pinfunction "5.ADC2_5") (pintype "bidirectional"))
      (node (ref "U$6") (pin "12.L") (pinfunction "12_12.L") (pintype "bidirectional"))
      (node (ref "U$6") (pin "12.R") (pinfunction "12_12.R") (pintype "bidirectional"))
      (node (ref "U4") (pin "12") (pinfunction "12.RB5_12") (pintype "bidirectional"))
    )
    (net (code "28") (name "RB6") (class "Default")
      (node (ref "R9") (pin "2") (pinfunction "2_2") (pintype "passive"))
      (node (ref "U$6") (pin "11.L") (pinfunction "11_11.L") (pintype "bidirectional"))
      (node (ref "U$6") (pin "11.R") (pinfunction "11_11.R") (pintype "bidirectional"))
      (node (ref "U4") (pin "11") (pinfunction "11.RB6_11") (pintype "bidirectional"))
    )
    (net (code "29") (name "RB7") (class "Default")
      (node (ref "J3") (pin "1") (pinfunction "1_1") (pintype "bidirectional"))
      (node (ref "U$6") (pin "10.L") (pinfunction "10_10.L") (pintype "bidirectional"))
      (node (ref "U$6") (pin "10.R") (pinfunction "10_10.R") (pintype "bidirectional"))
      (node (ref "U4") (pin "10") (pinfunction "10.RB7_10") (pintype "bidirectional"))
    )
    (net (code "30") (name "RC0") (class "Default")
      (node (ref "U$6") (pin "16.L") (pinfunction "16_16.L") (pintype "bidirectional"))
      (node (ref "U$6") (pin "16.R") (pinfunction "16_16.R") (pintype "bidirectional"))
      (node (ref "U$7") (pin "4") (pinfunction "4_4") (pintype "bidirectional"))
      (node (ref "U4") (pin "16") (pinfunction "16.RC0_16") (pintype "bidirectional"))
    )
    (net (code "31") (name "RC1") (class "Default")
      (node (ref "U$6") (pin "15.L") (pinfunction "15_15.L") (pintype "bidirectional"))
      (node (ref "U$6") (pin "15.R") (pinfunction "15_15.R") (pintype "bidirectional"))
      (node (ref "U$7") (pin "3") (pinfunction "3_3") (pintype "bidirectional"))
      (node (ref "U4") (pin "15") (pinfunction "15.RC1_15") (pintype "bidirectional"))
    )
    (net (code "32") (name "RC2") (class "Default")
      (node (ref "J202") (pin "3") (pinfunction "3.ADC0_3") (pintype "bidirectional"))
      (node (ref "U$6") (pin "14.L") (pinfunction "14_14.L") (pintype "bidirectional"))
      (node (ref "U$6") (pin "14.R") (pinfunction "14_14.R") (pintype "bidirectional"))
      (node (ref "U4") (pin "14") (pinfunction "14.RC2_14") (pintype "bidirectional"))
    )
    (net (code "33") (name "RC3") (class "Default")
      (node (ref "J202") (pin "4") (pinfunction "4.ADC1_4") (pintype "bidirectional"))
      (node (ref "U$6") (pin "7.L") (pinfunction "7_7.L") (pintype "bidirectional"))
      (node (ref "U$6") (pin "7.R") (pinfunction "7_7.R") (pintype "bidirectional"))
      (node (ref "U4") (pin "7") (pinfunction "7.RC3_7") (pintype "bidirectional"))
    )
    (net (code "34") (name "RC4") (class "Default")
      (node (ref "U$11") (pin "3.RXI") (pinfunction "(3)MCU.TX_3.RXI") (pintype "bidirectional"))
      (node (ref "U$6") (pin "6.L") (pinfunction "6_6.L") (pintype "bidirectional"))
      (node (ref "U$6") (pin "6.R") (pinfunction "6_6.R") (pintype "bidirectional"))
      (node (ref "U4") (pin "6") (pinfunction "6.RC4_6") (pintype "bidirectional"))
    )
    (net (code "35") (name "RC5") (class "Default")
      (node (ref "U$11") (pin "4.RDO") (pinfunction "(4)MCU.RX_4.RDO") (pintype "bidirectional"))
      (node (ref "U$6") (pin "5.L") (pinfunction "5_5.L") (pintype "bidirectional"))
      (node (ref "U$6") (pin "5.R") (pinfunction "5_5.R") (pintype "bidirectional"))
      (node (ref "U4") (pin "5") (pinfunction "5.RC5_5") (pintype "bidirectional"))
    )
    (net (code "36") (name "RC6") (class "Default")
      (node (ref "R6") (pin "1") (pinfunction "1_1") (pintype "passive"))
      (node (ref "U$6") (pin "8.L") (pinfunction "8_8.L") (pintype "bidirectional"))
      (node (ref "U$6") (pin "8.R") (pinfunction "8_8.R") (pintype "bidirectional"))
      (node (ref "U4") (pin "8") (pinfunction "8.RC6_8") (pintype "bidirectional"))
    )
    (net (code "37") (name "RC7") (class "Default")
      (node (ref "U$6") (pin "9.L") (pinfunction "9_9.L") (pintype "bidirectional"))
      (node (ref "U$6") (pin "9.R") (pinfunction "9_9.R") (pintype "bidirectional"))
      (node (ref "U$7") (pin "2") (pinfunction "2_2") (pintype "bidirectional"))
      (node (ref "U4") (pin "9") (pinfunction "9.RC7_9") (pintype "bidirectional"))
    )
    (net (code "38") (name "USB_5V_AT") (class "Default")
      (node (ref "D1") (pin "A") (pinfunction "A_A") (pintype "passive"))
    )
    (net (code "39") (name "USB_5V_PIC") (class "Default")
      (node (ref "D2") (pin "A") (pinfunction "A_A") (pintype "passive"))
    )
    (net (code "40") (name "VDD") (class "Default")
      (node (ref "C11") (pin "2") (pinfunction "+_2") (pintype "passive"))
      (node (ref "C12") (pin "2") (pinfunction "+_2") (pintype "passive"))
      (node (ref "C13") (pin "2") (pinfunction "+_2") (pintype "passive"))
      (node (ref "C14") (pin "2") (pinfunction "+_2") (pintype "passive"))
      (node (ref "C15") (pin "2") (pinfunction "+_2") (pintype "passive"))
      (node (ref "J202") (pin "2") (pinfunction "2.VDD_2") (pintype "bidirectional"))
      (node (ref "J203") (pin "2") (pinfunction "2.VDD(PWR)_2") (pintype "bidirectional"))
      (node (ref "LED201") (pin "3.+") (pinfunction "3.+_3.+") (pintype "passive"))
      (node (ref "R10") (pin "1") (pinfunction "1_1") (pintype "passive"))
      (node (ref "R7") (pin "1") (pinfunction "1_1") (pintype "passive"))
      (node (ref "R8") (pin "1") (pinfunction "1_1") (pintype "passive"))
      (node (ref "R9") (pin "1") (pinfunction "1_1") (pintype "passive"))
      (node (ref "U$6") (pin "1.L") (pinfunction "1_1.L") (pintype "bidirectional"))
      (node (ref "U$6") (pin "1.R") (pinfunction "1_1.R") (pintype "bidirectional"))
      (node (ref "U4") (pin "1") (pinfunction "1.VDD_1") (pintype "bidirectional"))
    )
    (net (code "41") (name "unconnected-(J1-1.GND-Pad1)") (class "Default")
      (node (ref "J1") (pin "1") (pinfunction "1.GND_1") (pintype "bidirectional"))
    )
    (net (code "42") (name "unconnected-(J1-2.VDD-Pad2)") (class "Default")
      (node (ref "J1") (pin "2") (pinfunction "2.VDD_2") (pintype "bidirectional"))
    )
    (net (code "43") (name "unconnected-(J1-3.DATA-Pad3)") (class "Default")
      (node (ref "J1") (pin "3") (pinfunction "3.DATA_3") (pintype "bidirectional"))
    )
    (net (code "44") (name "unconnected-(J2-1.GND-Pad1)") (class "Default")
      (node (ref "J2") (pin "1") (pinfunction "1.GND_1") (pintype "bidirectional"))
    )
    (net (code "45") (name "unconnected-(J2-2.VDD-Pad2)") (class "Default")
      (node (ref "J2") (pin "2") (pinfunction "2.VDD_2") (pintype "bidirectional"))
    )
    (net (code "46") (name "unconnected-(J2-3.DATA-Pad3)") (class "Default")
      (node (ref "J2") (pin "3") (pinfunction "3.DATA_3") (pintype "bidirectional"))
    )
    (net (code "47") (name "unconnected-(J203-6.PGM-Pad6)") (class "Default")
      (node (ref "J203") (pin "6") (pinfunction "6.PGM_6") (pintype "bidirectional"))
    )
    (net (code "48") (name "unconnected-(U$11-(1)3V3-Pad1.3V3)") (class "Default")
      (node (ref "U$11") (pin "1.3V3") (pinfunction "(1)3V3_1.3V3") (pintype "bidirectional"))
    )
    (net (code "49") (name "unconnected-(U$11-(2)DTR-Pad2.DTR)") (class "Default")
      (node (ref "U$11") (pin "2.DTR") (pinfunction "(2)DTR_2.DTR") (pintype "bidirectional"))
    )
    (net (code "50") (name "unconnected-(U$11-(5)GND-Pad5.GND)") (class "Default")
      (node (ref "U$11") (pin "5.GND") (pinfunction "(5)GND_5.GND") (pintype "bidirectional"))
    )
    (net (code "51") (name "unconnected-(U$11-(6)5V-Pad6.5V)") (class "Default")
      (node (ref "U$11") (pin "6.5V") (pinfunction "(6)5V_6.5V") (pintype "bidirectional"))
    )
  )
)
